# SFP.net
KiCad netlist of a schematic drawn in Altium Designer
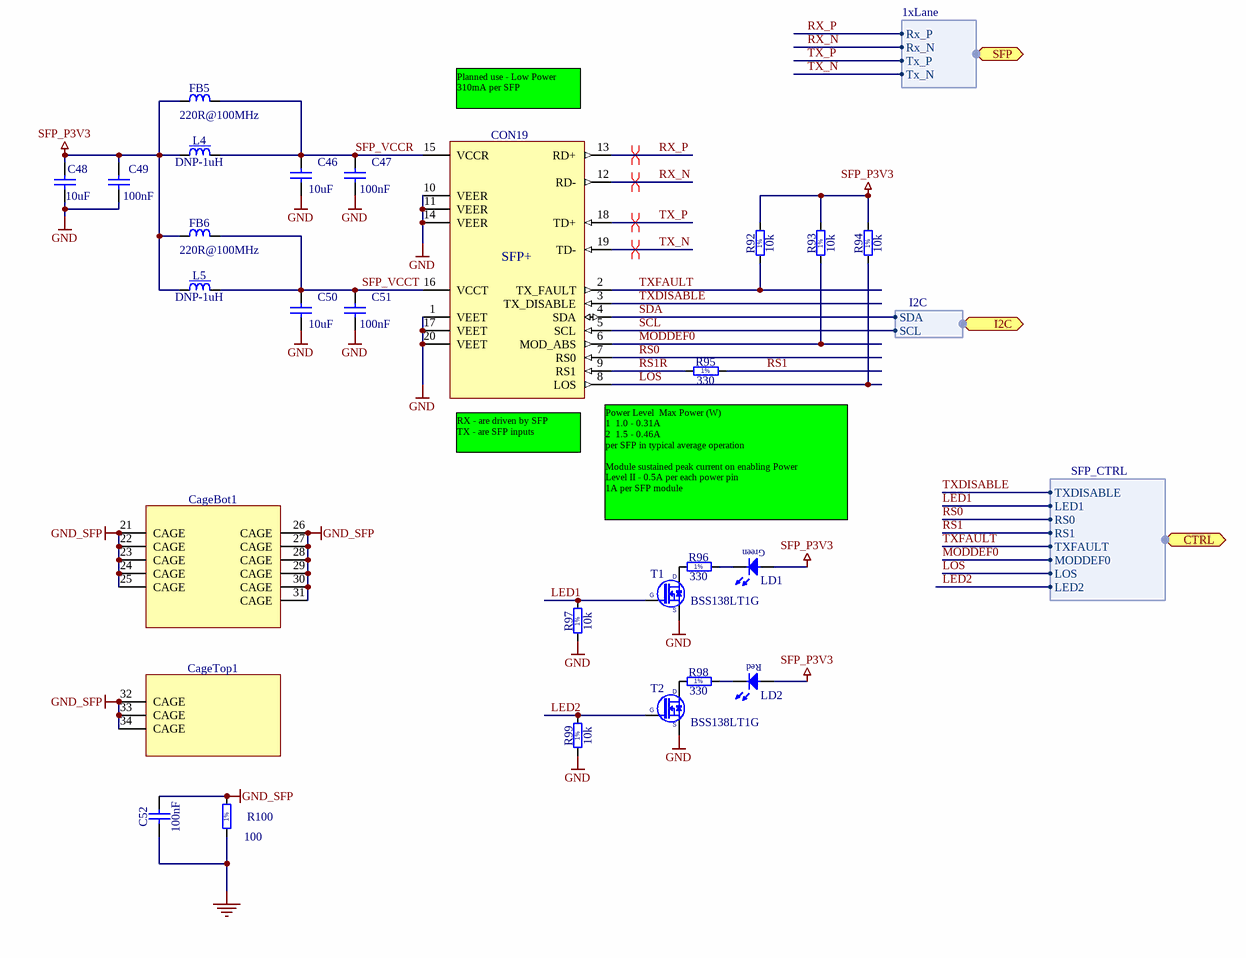
[diagram p0: SFP.SchDoc]

(export (version "E")
  (design (tool "Eeschema 10.0.6"))
  (components
    (comp (ref "C46")
      (value "10uF")
      (footprint "CAPC2012X135N")
      (description "Non-polarised capacitor")
      (fields
        (field (name "PART NUMBER") "CC0805_10UF_10V_10%_X7R")
        (field (name "VOLTAGE") "10V")
        (field (name "AUTHOR") "CERN DEM JLC")
      )
      (libsource (lib "Capacitors") (part "Capacitor - non polarized"))
    )
    (comp (ref "C47")
      (value "100nF")
      (footprint "CAPC1005X55N")
      (description "Non-polarised capacitor")
      (fields
        (field (name "PART NUMBER") "CC0402_100NF_16V_10%_X5R")
        (field (name "VOLTAGE") "16V")
        (field (name "AUTHOR") "CERN DEM JLC")
      )
      (libsource (lib "Capacitors") (part "Capacitor - non polarized"))
    )
    (comp (ref "C48")
      (value "10uF")
      (footprint "CAPC2012X135N")
      (description "Non-polarised capacitor")
      (fields
        (field (name "PART NUMBER") "CC0805_10UF_10V_10%_X7R")
        (field (name "VOLTAGE") "10V")
        (field (name "AUTHOR") "CERN DEM JLC")
      )
      (libsource (lib "Capacitors") (part "Capacitor - non polarized"))
    )
    (comp (ref "C49")
      (value "100nF")
      (footprint "CAPC1005X55N")
      (description "Non-polarised capacitor")
      (fields
        (field (name "PART NUMBER") "CC0402_100NF_16V_10%_X7R")
        (field (name "VOLTAGE") "16V")
        (field (name "AUTHOR") "CERN DEM JLC")
      )
      (libsource (lib "Capacitors") (part "Capacitor - non polarized"))
    )
    (comp (ref "C50")
      (value "10uF")
      (footprint "CAPC2012X135N")
      (description "Non-polarised capacitor")
      (fields
        (field (name "PART NUMBER") "CC0805_10UF_10V_10%_X7R")
        (field (name "VOLTAGE") "10V")
        (field (name "AUTHOR") "CERN DEM JLC")
      )
      (libsource (lib "Capacitors") (part "Capacitor - non polarized"))
    )
    (comp (ref "C51")
      (value "100nF")
      (footprint "CAPC1005X55N")
      (description "Non-polarised capacitor")
      (fields
        (field (name "PART NUMBER") "CC0402_100NF_16V_10%_X5R")
        (field (name "VOLTAGE") "16V")
        (field (name "AUTHOR") "CERN DEM JLC")
      )
      (libsource (lib "Capacitors") (part "Capacitor - non polarized"))
    )
    (comp (ref "C52")
      (value "100nF")
      (footprint "CAPC1005X55N")
      (description "Non-polarised capacitor")
      (fields
        (field (name "PART NUMBER") "CC0402_100NF_16V_10%_X5R")
        (field (name "VOLTAGE") "16V")
        (field (name "AUTHOR") "CERN DEM JLC")
      )
      (libsource (lib "Capacitors") (part "Capacitor - non polarized"))
    )
    (comp (ref "CageBot1")
      (value "6367034-1")
      (footprint "TYCO_6367034-1")
      (description "SFP  Cage Bottom (Small Form-factor Pluggable)")
      (fields
        (field (name "PART NUMBER") "TYCO_6367034-1")
        (field (name "MANUFACTURER") "TYCO ELECTRONICS")
        (field (name "AUTHOR") "CERN DEM JLC")
      )
      (libsource (lib "Connectors") (part "SFPx1_Cage Bottom"))
    )
    (comp (ref "CageTop1")
      (value "6367035-1")
      (footprint "TYCO_6367035-1")
      (description "SFP  Cage Top (Small Form-factor Pluggable)")
      (fields
        (field (name "PART NUMBER") "TYCO_6367035-1")
        (field (name "MANUFACTURER") "TYCO ELECTRONICS")
        (field (name "AUTHOR") "CERN DEM JLC")
      )
      (libsource (lib "Connectors") (part "SFPx1_Cage Top"))
    )
    (comp (ref "CON19")
      (value "1888247-1")
      (footprint "TYCO_1888247-1")
      (description "20 Position SFP+ Connector (Small Form-factor Pluggable)")
      (fields
        (field (name "PART NUMBER") "TYCO_1888247-1")
        (field (name "MANUFACTURER") "TYCO ELECTRONICS")
        (field (name "AUTHOR") "CERN DEM JLC")
      )
      (libsource (lib "Connectors") (part "SFP+x1"))
    )
    (comp (ref "FB5")
      (value "220R@100MHz")
      (footprint "INDC2012X105N")
      (description "Inductor")
      (fields
        (field (name "PART NUMBER") "IND0805_MURATA_BLM21PG221SN1D")
        (field (name "POWER") "2A")
        (field (name "AUTHOR") "CERN DEM JLC")
      )
      (libsource (lib "Inductors & Transformers") (part "Inductor"))
    )
    (comp (ref "FB6")
      (value "220R@100MHz")
      (footprint "INDC2012X105N")
      (description "Inductor")
      (fields
        (field (name "PART NUMBER") "IND0805_MURATA_BLM21PG221SN1D")
        (field (name "POWER") "2A")
        (field (name "AUTHOR") "CERN DEM JLC")
      )
      (libsource (lib "Inductors & Transformers") (part "Inductor"))
    )
    (comp (ref "L4")
      (value "DNP-1uH")
      (footprint "IND_MURATA_LQH32")
      (description "Inductor With Magnetic core")
      (fields
        (field (name "PART NUMBER") "IND_1UH_20%_MURATA_LQH32CN1R0M33")
        (field (name "POWER") "1A")
        (field (name "AUTHOR") "CERN DEM JLC")
      )
      (libsource (lib "Inductors & Transformers") (part "Inductor With Magnetic core"))
    )
    (comp (ref "L5")
      (value "DNP-1uH")
      (footprint "IND_MURATA_LQH32")
      (description "Inductor With Magnetic core")
      (fields
        (field (name "PART NUMBER") "IND_1UH_20%_MURATA_LQH32CN1R0M33")
        (field (name "POWER") "1A")
        (field (name "AUTHOR") "CERN DEM JLC")
      )
      (libsource (lib "Inductors & Transformers") (part "Inductor With Magnetic core"))
    )
    (comp (ref "LD1")
      (value "LED_AVAGO_HSME-C120")
      (footprint "LED_AVAGO_HSME-C120")
      (description "LED Green 1C 2A")
      (fields
        (field (name "MANUFACTURER") "AVAGO TECHNOLOGIES")
        (field (name "MANUFACTURER PART NUMBER") "HSME-C120")
        (field (name "AUTHOR") "CERN DEM JMW")
      )
      (libsource (lib "ICs And Semiconductors") (part "LED Green 1C 2A"))
    )
    (comp (ref "LD2")
      (value "LED_AVAGO_HSMC-C120")
      (footprint "LED_AVAGO_HSMC-C120")
      (description "LED Red 1C 2A")
      (fields
        (field (name "MANUFACTURER") "AVAGO TECHNOLOGIES")
        (field (name "MANUFACTURER PART NUMBER") "HSMC-C120")
        (field (name "AUTHOR") "CERN DEM JMW")
      )
      (libsource (lib "ICs And Semiconductors") (part "LED Red 1C 2A"))
    )
    (comp (ref "R92")
      (value "10k")
      (footprint "RESC1005X40N")
      (description "Resistor - 1%")
      (fields
        (field (name "PART NUMBER") "R0402_10K_1%_0.0625W_100PPM")
        (field (name "POWER") "0.0625W")
        (field (name "AUTHOR") "CERN DEM JLC")
      )
      (libsource (lib "Resistors") (part "Resistor - 1%"))
    )
    (comp (ref "R93")
      (value "10k")
      (footprint "RESC1005X40N")
      (description "Resistor - 1%")
      (fields
        (field (name "PART NUMBER") "R0402_10K_1%_0.0625W_100PPM")
        (field (name "POWER") "0.0625W")
        (field (name "AUTHOR") "CERN DEM JLC")
      )
      (libsource (lib "Resistors") (part "Resistor - 1%"))
    )
    (comp (ref "R94")
      (value "10k")
      (footprint "RESC1005X40N")
      (description "Resistor - 1%")
      (fields
        (field (name "PART NUMBER") "R0402_10K_1%_0.0625W_100PPM")
        (field (name "POWER") "0.0625W")
        (field (name "AUTHOR") "CERN DEM JLC")
      )
      (libsource (lib "Resistors") (part "Resistor - 1%"))
    )
    (comp (ref "R95")
      (value "330")
      (footprint "RESC1608X55N")
      (description "Resistor - 1%")
      (fields
        (field (name "PART NUMBER") "R0603_330R_1%_0.1W_100PPM")
        (field (name "POWER") "0.1W")
        (field (name "AUTHOR") "CERN DEM JLC")
      )
      (libsource (lib "Resistors") (part "Resistor - 1%"))
    )
    (comp (ref "R96")
      (value "330")
      (footprint "RESC1608X55N")
      (description "Resistor - 1%")
      (fields
        (field (name "PART NUMBER") "R0603_330R_1%_0.1W_100PPM")
        (field (name "POWER") "0.1W")
        (field (name "AUTHOR") "CERN DEM JLC")
      )
      (libsource (lib "Resistors") (part "Resistor - 1%"))
    )
    (comp (ref "R97")
      (value "10k")
      (footprint "RESC1005X40N")
      (description "Resistor - 1%")
      (fields
        (field (name "PART NUMBER") "R0402_10K_1%_0.0625W_100PPM")
        (field (name "POWER") "0.0625W")
        (field (name "AUTHOR") "CERN DEM JLC")
      )
      (libsource (lib "Resistors") (part "Resistor - 1%"))
    )
    (comp (ref "R98")
      (value "330")
      (footprint "RESC1608X55N")
      (description "Resistor - 1%")
      (fields
        (field (name "PART NUMBER") "R0603_330R_1%_0.1W_100PPM")
        (field (name "POWER") "0.1W")
        (field (name "AUTHOR") "CERN DEM JLC")
      )
      (libsource (lib "Resistors") (part "Resistor - 1%"))
    )
    (comp (ref "R99")
      (value "10k")
      (footprint "RESC1005X40N")
      (description "Resistor - 1%")
      (fields
        (field (name "PART NUMBER") "R0402_10K_1%_0.0625W_100PPM")
        (field (name "POWER") "0.0625W")
        (field (name "AUTHOR") "CERN DEM JLC")
      )
      (libsource (lib "Resistors") (part "Resistor - 1%"))
    )
    (comp (ref "R100")
      (value "100")
      (footprint "RESC1005X40N")
      (description "Resistor - 1%")
      (fields
        (field (name "PART NUMBER") "R0402_100R_1%_0.0625W_100PPM")
        (field (name "POWER") "0.0625W")
        (field (name "AUTHOR") "CERN DEM JLC")
      )
      (libsource (lib "Resistors") (part "Resistor - 1%"))
    )
    (comp (ref "T1")
      (value "BSS138LT1G")
      (footprint "SOT95P240X110-3N")
      (description "N-CHANNEL MOSFET WITH DIODE")
      (fields (field (name "MANUFACTURER") "ON SEMICONDUCTOR") (field (name "AUTHOR") "CERN DEM JLC"))
      (libsource (lib "ICs And Semiconductors") (part "N-MOSFET-D 1G 2S 3D"))
    )
    (comp (ref "T2")
      (value "BSS138LT1G")
      (footprint "SOT95P240X110-3N")
      (description "N-CHANNEL MOSFET WITH DIODE")
      (fields (field (name "MANUFACTURER") "ON SEMICONDUCTOR") (field (name "AUTHOR") "CERN DEM JLC"))
      (libsource (lib "ICs And Semiconductors") (part "N-MOSFET-D 1G 2S 3D"))
    )
  )
  (nets
    (net (code "4") (name "/LED1") (class "Default")
      (node (ref "R97") (pin "2") (pinfunction "2_2") (pintype "passive"))
      (node (ref "T1") (pin "1") (pinfunction "G_1") (pintype "passive"))
    )
    (net (code "5") (name "/LED2") (class "Default")
      (node (ref "R99") (pin "2") (pinfunction "2_2") (pintype "passive"))
      (node (ref "T2") (pin "1") (pinfunction "G_1") (pintype "passive"))
    )
    (net (code "6") (name "/LOS") (class "Default")
      (node (ref "CON19") (pin "8") (pinfunction "LOS_8") (pintype "output"))
      (node (ref "R94") (pin "1") (pinfunction "1_1") (pintype "passive"))
    )
    (net (code "7") (name "/MODDEF0") (class "Default")
      (node (ref "CON19") (pin "6") (pinfunction "MOD_ABS_6") (pintype "output"))
      (node (ref "R93") (pin "1") (pinfunction "1_1") (pintype "passive"))
    )
    (net (code "8") (name "/RS0") (class "Default")
      (node (ref "CON19") (pin "7") (pinfunction "RS0_7") (pintype "input"))
    )
    (net (code "9") (name "/RS1") (class "Default")
      (node (ref "R95") (pin "2") (pinfunction "2_2") (pintype "passive"))
    )
    (net (code "10") (name "/RS1R") (class "Default")
      (node (ref "CON19") (pin "9") (pinfunction "RS1_9") (pintype "input"))
      (node (ref "R95") (pin "1") (pinfunction "1_1") (pintype "passive"))
    )
    (net (code "11") (name "/RX_N") (class "Default")
      (node (ref "CON19") (pin "12") (pinfunction "RD-_12") (pintype "output"))
    )
    (net (code "12") (name "/RX_P") (class "Default")
      (node (ref "CON19") (pin "13") (pinfunction "RD+_13") (pintype "output"))
    )
    (net (code "13") (name "/SCL") (class "Default")
      (node (ref "CON19") (pin "5") (pinfunction "SCL_5") (pintype "input"))
    )
    (net (code "14") (name "/SDA") (class "Default")
      (node (ref "CON19") (pin "4") (pinfunction "SDA_4") (pintype "bidirectional"))
    )
    (net (code "15") (name "/SFP_VCCR") (class "Default")
      (node (ref "C46") (pin "1") (pinfunction "1_1") (pintype "passive"))
      (node (ref "C47") (pin "2") (pinfunction "2_2") (pintype "passive"))
      (node (ref "CON19") (pin "15") (pinfunction "VCCR_15") (pintype "power_in"))
      (node (ref "FB5") (pin "2") (pinfunction "2_2") (pintype "passive"))
      (node (ref "L4") (pin "2") (pinfunction "2_2") (pintype "passive"))
    )
    (net (code "16") (name "/SFP_VCCT") (class "Default")
      (node (ref "C50") (pin "1") (pinfunction "1_1") (pintype "passive"))
      (node (ref "C51") (pin "2") (pinfunction "2_2") (pintype "passive"))
      (node (ref "CON19") (pin "16") (pinfunction "VCCT_16") (pintype "power_in"))
      (node (ref "FB6") (pin "2") (pinfunction "2_2") (pintype "passive"))
      (node (ref "L5") (pin "2") (pinfunction "2_2") (pintype "passive"))
    )
    (net (code "17") (name "/TXDISABLE") (class "Default")
      (node (ref "CON19") (pin "3") (pinfunction "TX_DISABLE_3") (pintype "input"))
    )
    (net (code "18") (name "/TXFAULT") (class "Default")
      (node (ref "CON19") (pin "2") (pinfunction "TX_FAULT_2") (pintype "output"))
      (node (ref "R92") (pin "1") (pinfunction "1_1") (pintype "passive"))
    )
    (net (code "19") (name "/TX_N") (class "Default")
      (node (ref "CON19") (pin "19") (pinfunction "TD-_19") (pintype "input"))
    )
    (net (code "20") (name "/TX_P") (class "Default")
      (node (ref "CON19") (pin "18") (pinfunction "TD+_18") (pintype "input"))
    )
    (net (code "24") (name "GND") (class "Default")
      (node (ref "C46") (pin "2") (pinfunction "2_2") (pintype "passive"))
      (node (ref "C47") (pin "1") (pinfunction "1_1") (pintype "passive"))
      (node (ref "C48") (pin "2") (pinfunction "2_2") (pintype "passive"))
      (node (ref "C49") (pin "2") (pinfunction "2_2") (pintype "passive"))
      (node (ref "C50") (pin "2") (pinfunction "2_2") (pintype "passive"))
      (node (ref "C51") (pin "1") (pinfunction "1_1") (pintype "passive"))
      (node (ref "C52") (pin "1") (pinfunction "1_1") (pintype "passive"))
      (node (ref "CON19") (pin "1") (pinfunction "VEET_1") (pintype "power_in"))
      (node (ref "CON19") (pin "10") (pinfunction "VEER_10") (pintype "power_in"))
      (node (ref "CON19") (pin "11") (pinfunction "VEER_11") (pintype "power_in"))
      (node (ref "CON19") (pin "14") (pinfunction "VEER_14") (pintype "power_in"))
      (node (ref "CON19") (pin "17") (pinfunction "VEET_17") (pintype "power_in"))
      (node (ref "CON19") (pin "20") (pinfunction "VEET_20") (pintype "power_in"))
      (node (ref "R100") (pin "1") (pinfunction "1_1") (pintype "passive"))
      (node (ref "R97") (pin "1") (pinfunction "1_1") (pintype "passive"))
      (node (ref "R99") (pin "1") (pinfunction "1_1") (pintype "passive"))
      (node (ref "T1") (pin "2") (pinfunction "S_2") (pintype "passive"))
      (node (ref "T2") (pin "2") (pinfunction "S_2") (pintype "passive"))
    )
    (net (code "25") (name "GND_SFP") (class "Default")
      (node (ref "C52") (pin "2") (pinfunction "2_2") (pintype "passive"))
      (node (ref "CageBot1") (pin "21") (pinfunction "CAGE_21") (pintype "power_in"))
      (node (ref "CageBot1") (pin "22") (pinfunction "CAGE_22") (pintype "power_in"))
      (node (ref "CageBot1") (pin "23") (pinfunction "CAGE_23") (pintype "power_in"))
      (node (ref "CageBot1") (pin "24") (pinfunction "CAGE_24") (pintype "power_in"))
      (node (ref "CageBot1") (pin "25") (pinfunction "CAGE_25") (pintype "power_in"))
      (node (ref "CageBot1") (pin "26") (pinfunction "CAGE_26") (pintype "power_in"))
      (node (ref "CageBot1") (pin "27") (pinfunction "CAGE_27") (pintype "power_in"))
      (node (ref "CageBot1") (pin "28") (pinfunction "CAGE_28") (pintype "power_in"))
      (node (ref "CageBot1") (pin "29") (pinfunction "CAGE_29") (pintype "power_in"))
      (node (ref "CageBot1") (pin "30") (pinfunction "CAGE_30") (pintype "power_in"))
      (node (ref "CageBot1") (pin "31") (pinfunction "CAGE_31") (pintype "power_in"))
      (node (ref "CageTop1") (pin "32") (pinfunction "CAGE_32") (pintype "power_in"))
      (node (ref "CageTop1") (pin "33") (pinfunction "CAGE_33") (pintype "power_in"))
      (node (ref "CageTop1") (pin "34") (pinfunction "CAGE_34") (pintype "power_in"))
      (node (ref "R100") (pin "2") (pinfunction "2_2") (pintype "passive"))
    )
    (net (code "26") (name "Net-(LD1-C)") (class "Default")
      (node (ref "LD1") (pin "1") (pinfunction "C_1") (pintype "passive"))
      (node (ref "R96") (pin "2") (pinfunction "2_2") (pintype "passive"))
    )
    (net (code "27") (name "Net-(LD2-C)") (class "Default")
      (node (ref "LD2") (pin "1") (pinfunction "C_1") (pintype "passive"))
      (node (ref "R98") (pin "2") (pinfunction "2_2") (pintype "passive"))
    )
    (net (code "28") (name "Net-(T1-D)") (class "Default")
      (node (ref "R96") (pin "1") (pinfunction "1_1") (pintype "passive"))
      (node (ref "T1") (pin "3") (pinfunction "D_3") (pintype "passive"))
    )
    (net (code "29") (name "Net-(T2-D)") (class "Default")
      (node (ref "R98") (pin "1") (pinfunction "1_1") (pintype "passive"))
      (node (ref "T2") (pin "3") (pinfunction "D_3") (pintype "passive"))
    )
    (net (code "30") (name "SFP_P3V3") (class "Default")
      (node (ref "C48") (pin "1") (pinfunction "1_1") (pintype "passive"))
      (node (ref "C49") (pin "1") (pinfunction "1_1") (pintype "passive"))
      (node (ref "FB5") (pin "1") (pinfunction "1_1") (pintype "passive"))
      (node (ref "FB6") (pin "1") (pinfunction "1_1") (pintype "passive"))
      (node (ref "L4") (pin "1") (pinfunction "1_1") (pintype "passive"))
      (node (ref "L5") (pin "1") (pinfunction "1_1") (pintype "passive"))
      (node (ref "LD1") (pin "2") (pinfunction "A_2") (pintype "passive"))
      (node (ref "LD2") (pin "2") (pinfunction "A_2") (pintype "passive"))
      (node (ref "R92") (pin "2") (pinfunction "2_2") (pintype "passive"))
      (node (ref "R93") (pin "2") (pinfunction "2_2") (pintype "passive"))
      (node (ref "R94") (pin "2") (pinfunction "2_2") (pintype "passive"))
    )
  )
)
